# CUSP_PI_Hat.net
KiCad netlist of a schematic drawn in Altium Designer
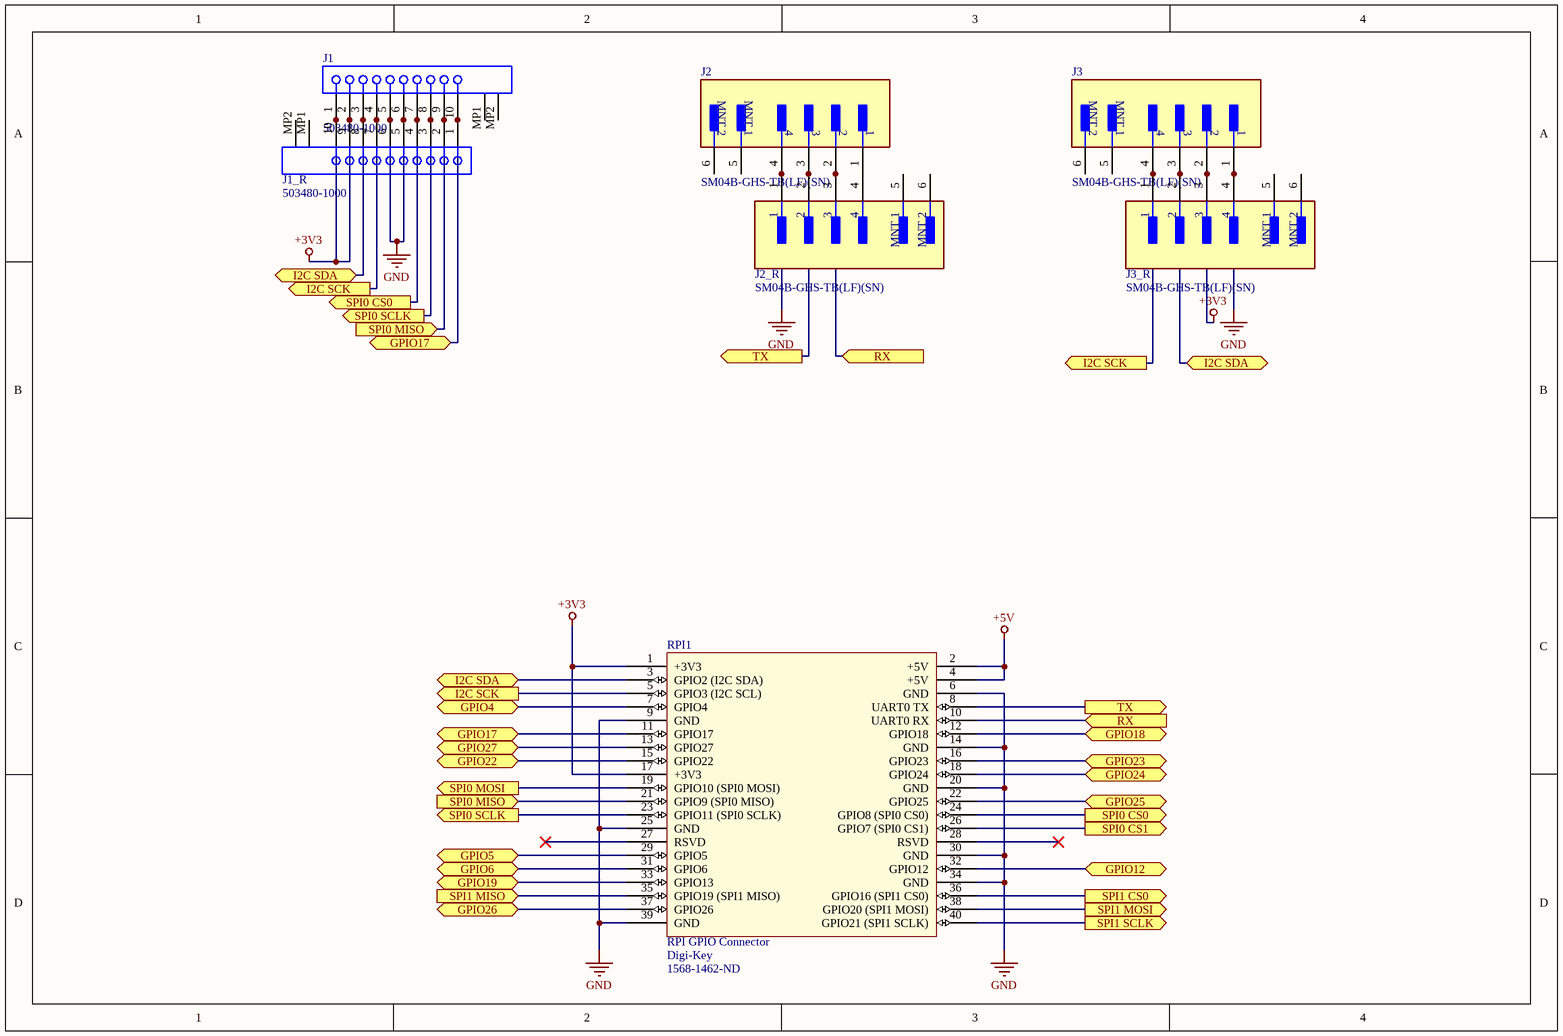
[diagram p0: CUSP_PI_Hat.SchDoc]

(export (version "E")
  (design (tool "Eeschema 10.0.6"))
  (components
    (comp (ref "J1")
      (value "503480-1000")
      (footprint "MOLX-503480-1000")
      (fields (field (name "MANUFACTURER") "Molex"))
      (libsource (lib "Altium Content Vault") (part "MOLX-503480-1000"))
    )
    (comp (ref "J1_R")
      (value "503480-1000")
      (footprint "MOLX-503480-1000")
      (fields (field (name "MANUFACTURER") "Molex"))
      (libsource (lib "") (part "MOLX-503480-1000_1"))
    )
    (comp (ref "J2")
      (value "SM04B-GHS-TB(LF)(SN)")
      (footprint "FP-SM04B-GHS-TB_LF_SN-MFG")
      (description "CONN HEADER SMD R/A 4POS 1.25MM")
      (libsource (lib "Altium Content Vault") (part "f4320a1371cd6270e33bce1916c33c0"))
    )
    (comp (ref "J2_R")
      (value "SM04B-GHS-TB(LF)(SN)")
      (footprint "FP-SM04B-GHS-TB_LF_SN-MFG")
      (description "CONN HEADER SMD R/A 4POS 1.25MM")
      (libsource (lib "") (part "f4320a1371cd6270e33bce1916c33c0_1"))
    )
    (comp (ref "J3")
      (value "SM04B-GHS-TB(LF)(SN)")
      (footprint "FP-SM04B-GHS-TB_LF_SN-MFG")
      (description "CONN HEADER SMD R/A 4POS 1.25MM")
      (libsource (lib "Altium Content Vault") (part "f4320a1371cd6270e33bce1916c33c0"))
    )
    (comp (ref "J3_R")
      (value "SM04B-GHS-TB(LF)(SN)")
      (footprint "FP-SM04B-GHS-TB_LF_SN-MFG")
      (description "CONN HEADER SMD R/A 4POS 1.25MM")
      (libsource (lib "") (part "f4320a1371cd6270e33bce1916c33c0_1"))
    )
    (comp (ref "RPI1")
      (value "RPI GPIO Connector")
      (footprint "rpi")
      (description "GPIO Header for Raspberry Pi A+/B+/Pi 2/Pi 3 - 2x20")
      (fields
        (field (name "MANUFACTURER") "SparkFun Electronics")
        (field (name "MANUFACTURER PART NUMBER") "PRT-14017")
        (field (name "SUPPLIER 1") "Digi-Key")
        (field (name "SUPPLIER PART NUMBER 1") "1568-1462-ND")
      )
      (libsource (lib "rpi") (part "rpi connector"))
    )
  )
  (nets
    (net (code "1") (name "+3V3") (class "Default")
      (node (ref "J1") (pin "1") (pinfunction "1_1") (pintype "passive"))
      (node (ref "J1") (pin "2") (pinfunction "2_2") (pintype "passive"))
      (node (ref "J1_R") (pin "10") (pinfunction "10_10") (pintype "passive"))
      (node (ref "J1_R") (pin "9") (pinfunction "9_9") (pintype "passive"))
      (node (ref "J3") (pin "2") (pinfunction "2_2") (pintype "passive"))
      (node (ref "J3_R") (pin "3") (pinfunction "3_3") (pintype "passive"))
      (node (ref "RPI1") (pin "1") (pinfunction "+3V3_1") (pintype "power_in"))
      (node (ref "RPI1") (pin "17") (pinfunction "+3V3_17") (pintype "power_in"))
    )
    (net (code "2") (name "+5V") (class "Default")
      (node (ref "RPI1") (pin "2") (pinfunction "+5V_2") (pintype "power_in"))
      (node (ref "RPI1") (pin "4") (pinfunction "+5V_4") (pintype "power_in"))
    )
    (net (code "3") (name "/GPIO4") (class "Default")
      (node (ref "RPI1") (pin "7") (pinfunction "GPIO4_7") (pintype "bidirectional"))
    )
    (net (code "4") (name "/GPIO5") (class "Default")
      (node (ref "RPI1") (pin "29") (pinfunction "GPIO5_29") (pintype "bidirectional"))
    )
    (net (code "5") (name "/GPIO6") (class "Default")
      (node (ref "RPI1") (pin "31") (pinfunction "GPIO6_31") (pintype "bidirectional"))
    )
    (net (code "6") (name "/GPIO12") (class "Default")
      (node (ref "RPI1") (pin "32") (pinfunction "GPIO12_32") (pintype "bidirectional"))
    )
    (net (code "7") (name "/GPIO17") (class "Default")
      (node (ref "J1") (pin "10") (pinfunction "10_10") (pintype "passive"))
      (node (ref "J1_R") (pin "1") (pinfunction "1_1") (pintype "passive"))
      (node (ref "RPI1") (pin "11") (pinfunction "GPIO17_11") (pintype "bidirectional"))
    )
    (net (code "8") (name "/GPIO18") (class "Default")
      (node (ref "RPI1") (pin "12") (pinfunction "GPIO18_12") (pintype "bidirectional"))
    )
    (net (code "9") (name "/GPIO19") (class "Default")
      (node (ref "RPI1") (pin "33") (pinfunction "GPIO13_33") (pintype "bidirectional"))
    )
    (net (code "10") (name "/GPIO22") (class "Default")
      (node (ref "RPI1") (pin "15") (pinfunction "GPIO22_15") (pintype "bidirectional"))
    )
    (net (code "11") (name "/GPIO23") (class "Default")
      (node (ref "RPI1") (pin "16") (pinfunction "GPIO23_16") (pintype "bidirectional"))
    )
    (net (code "12") (name "/GPIO24") (class "Default")
      (node (ref "RPI1") (pin "18") (pinfunction "GPIO24_18") (pintype "bidirectional"))
    )
    (net (code "13") (name "/GPIO25") (class "Default")
      (node (ref "RPI1") (pin "22") (pinfunction "GPIO25_22") (pintype "bidirectional"))
    )
    (net (code "14") (name "/GPIO26") (class "Default")
      (node (ref "RPI1") (pin "37") (pinfunction "GPIO26_37") (pintype "bidirectional"))
    )
    (net (code "15") (name "/GPIO27") (class "Default")
      (node (ref "RPI1") (pin "13") (pinfunction "GPIO27_13") (pintype "bidirectional"))
    )
    (net (code "16") (name "/I2C SCK") (class "Default")
      (node (ref "J1") (pin "4") (pinfunction "4_4") (pintype "passive"))
      (node (ref "J1_R") (pin "7") (pinfunction "7_7") (pintype "passive"))
      (node (ref "J3") (pin "4") (pinfunction "4_4") (pintype "passive"))
      (node (ref "J3_R") (pin "1") (pinfunction "1_1") (pintype "passive"))
      (node (ref "RPI1") (pin "5") (pinfunction "GPIO3_(I2C_SCL)_5") (pintype "bidirectional"))
    )
    (net (code "17") (name "/I2C SDA") (class "Default")
      (node (ref "J1") (pin "3") (pinfunction "3_3") (pintype "passive"))
      (node (ref "J1_R") (pin "8") (pinfunction "8_8") (pintype "passive"))
      (node (ref "J3") (pin "3") (pinfunction "3_3") (pintype "passive"))
      (node (ref "J3_R") (pin "2") (pinfunction "2_2") (pintype "passive"))
      (node (ref "RPI1") (pin "3") (pinfunction "GPIO2_(I2C_SDA)_3") (pintype "bidirectional"))
    )
    (net (code "18") (name "/RX") (class "Default")
      (node (ref "J2") (pin "2") (pinfunction "2_2") (pintype "passive"))
      (node (ref "J2_R") (pin "3") (pinfunction "3_3") (pintype "passive"))
      (node (ref "RPI1") (pin "10") (pinfunction "UART0_RX_10") (pintype "bidirectional"))
    )
    (net (code "19") (name "/SPI0 CS0") (class "Default")
      (node (ref "J1") (pin "7") (pinfunction "7_7") (pintype "passive"))
      (node (ref "J1_R") (pin "4") (pinfunction "4_4") (pintype "passive"))
      (node (ref "RPI1") (pin "24") (pinfunction "GPIO8_(SPI0_CS0)_24") (pintype "bidirectional"))
    )
    (net (code "20") (name "/SPI0 CS1") (class "Default")
      (node (ref "RPI1") (pin "26") (pinfunction "GPIO7_(SPI0_CS1)_26") (pintype "bidirectional"))
    )
    (net (code "21") (name "/SPI0 MISO") (class "Default")
      (node (ref "J1") (pin "9") (pinfunction "9_9") (pintype "passive"))
      (node (ref "J1_R") (pin "2") (pinfunction "2_2") (pintype "passive"))
      (node (ref "RPI1") (pin "21") (pinfunction "GPIO9_(SPI0_MISO)_21") (pintype "bidirectional"))
    )
    (net (code "22") (name "/SPI0 MOSI") (class "Default")
      (node (ref "RPI1") (pin "19") (pinfunction "GPIO10_(SPI0_MOSI)_19") (pintype "bidirectional"))
    )
    (net (code "23") (name "/SPI0 SCLK") (class "Default")
      (node (ref "J1") (pin "8") (pinfunction "8_8") (pintype "passive"))
      (node (ref "J1_R") (pin "3") (pinfunction "3_3") (pintype "passive"))
      (node (ref "RPI1") (pin "23") (pinfunction "GPIO11_(SPI0_SCLK)_23") (pintype "bidirectional"))
    )
    (net (code "24") (name "/SPI1 CS0") (class "Default")
      (node (ref "RPI1") (pin "36") (pinfunction "GPIO16_(SPI1_CS0)_36") (pintype "bidirectional"))
    )
    (net (code "25") (name "/SPI1 MISO") (class "Default")
      (node (ref "RPI1") (pin "35") (pinfunction "GPIO19_(SPI1_MISO)_35") (pintype "bidirectional"))
    )
    (net (code "26") (name "/SPI1 MOSI") (class "Default")
      (node (ref "RPI1") (pin "38") (pinfunction "GPIO20_(SPI1_MOSI)_38") (pintype "bidirectional"))
    )
    (net (code "27") (name "/SPI1 SCLK") (class "Default")
      (node (ref "RPI1") (pin "40") (pinfunction "GPIO21_(SPI1_SCLK)_40") (pintype "bidirectional"))
    )
    (net (code "28") (name "/TX") (class "Default")
      (node (ref "J2") (pin "3") (pinfunction "3_3") (pintype "passive"))
      (node (ref "J2_R") (pin "2") (pinfunction "2_2") (pintype "passive"))
      (node (ref "RPI1") (pin "8") (pinfunction "UART0_TX_8") (pintype "bidirectional"))
    )
    (net (code "29") (name "GND") (class "Default")
      (node (ref "J1") (pin "5") (pinfunction "5_5") (pintype "passive"))
      (node (ref "J1") (pin "6") (pinfunction "6_6") (pintype "passive"))
      (node (ref "J1_R") (pin "5") (pinfunction "5_5") (pintype "passive"))
      (node (ref "J1_R") (pin "6") (pinfunction "6_6") (pintype "passive"))
      (node (ref "J2") (pin "4") (pinfunction "4_4") (pintype "passive"))
      (node (ref "J2_R") (pin "1") (pinfunction "1_1") (pintype "passive"))
      (node (ref "J3") (pin "1") (pinfunction "1_1") (pintype "passive"))
      (node (ref "J3_R") (pin "4") (pinfunction "4_4") (pintype "passive"))
      (node (ref "RPI1") (pin "14") (pinfunction "GND_14") (pintype "power_in"))
      (node (ref "RPI1") (pin "20") (pinfunction "GND_20") (pintype "power_in"))
      (node (ref "RPI1") (pin "25") (pinfunction "GND_25") (pintype "power_in"))
      (node (ref "RPI1") (pin "30") (pinfunction "GND_30") (pintype "power_in"))
      (node (ref "RPI1") (pin "34") (pinfunction "GND_34") (pintype "passive"))
      (node (ref "RPI1") (pin "39") (pinfunction "GND_39") (pintype "power_in"))
      (node (ref "RPI1") (pin "6") (pinfunction "GND_6") (pintype "power_in"))
      (node (ref "RPI1") (pin "9") (pinfunction "GND_9") (pintype "power_in"))
    )
    (net (code "30") (name "Net-(J2-Pad1)") (class "Default")
      (node (ref "J2") (pin "1") (pinfunction "1_1") (pintype "passive"))
      (node (ref "J2_R") (pin "4") (pinfunction "4_4") (pintype "passive"))
    )
    (net (code "31") (name "unconnected-(J1-PadMP1)") (class "Default")
      (node (ref "J1") (pin "MP1") (pinfunction "MP1_MP1") (pintype "passive"))
    )
    (net (code "32") (name "unconnected-(J1-PadMP2)") (class "Default")
      (node (ref "J1") (pin "MP2") (pinfunction "MP2_MP2") (pintype "passive"))
    )
    (net (code "33") (name "unconnected-(J1_R-PadMP1)") (class "Default")
      (node (ref "J1_R") (pin "MP1") (pinfunction "MP1_MP1") (pintype "passive"))
    )
    (net (code "34") (name "unconnected-(J1_R-PadMP2)") (class "Default")
      (node (ref "J1_R") (pin "MP2") (pinfunction "MP2_MP2") (pintype "passive"))
    )
    (net (code "35") (name "unconnected-(J2-MNT_1-Pad5)") (class "Default")
      (node (ref "J2") (pin "5") (pinfunction "MNT_1_5") (pintype "passive"))
    )
    (net (code "36") (name "unconnected-(J2-MNT_2-Pad6)") (class "Default")
      (node (ref "J2") (pin "6") (pinfunction "MNT_2_6") (pintype "passive"))
    )
    (net (code "37") (name "unconnected-(J2_R-MNT_1-Pad5)") (class "Default")
      (node (ref "J2_R") (pin "5") (pinfunction "MNT_1_5") (pintype "passive"))
    )
    (net (code "38") (name "unconnected-(J2_R-MNT_2-Pad6)") (class "Default")
      (node (ref "J2_R") (pin "6") (pinfunction "MNT_2_6") (pintype "passive"))
    )
    (net (code "39") (name "unconnected-(J3-MNT_1-Pad5)") (class "Default")
      (node (ref "J3") (pin "5") (pinfunction "MNT_1_5") (pintype "passive"))
    )
    (net (code "40") (name "unconnected-(J3-MNT_2-Pad6)") (class "Default")
      (node (ref "J3") (pin "6") (pinfunction "MNT_2_6") (pintype "passive"))
    )
    (net (code "41") (name "unconnected-(J3_R-MNT_1-Pad5)") (class "Default")
      (node (ref "J3_R") (pin "5") (pinfunction "MNT_1_5") (pintype "passive"))
    )
    (net (code "42") (name "unconnected-(J3_R-MNT_2-Pad6)") (class "Default")
      (node (ref "J3_R") (pin "6") (pinfunction "MNT_2_6") (pintype "passive"))
    )
    (net (code "43") (name "unconnected-(RPI1-RSVD-Pad27)") (class "Default")
      (node (ref "RPI1") (pin "27") (pinfunction "RSVD_27") (pintype "passive+no_connect"))
    )
    (net (code "44") (name "unconnected-(RPI1-RSVD-Pad28)") (class "Default")
      (node (ref "RPI1") (pin "28") (pinfunction "RSVD_28") (pintype "passive+no_connect"))
    )
  )
)
